# Arduino_nano_v3.net
KiCad netlist of a schematic drawn in Altium Designer
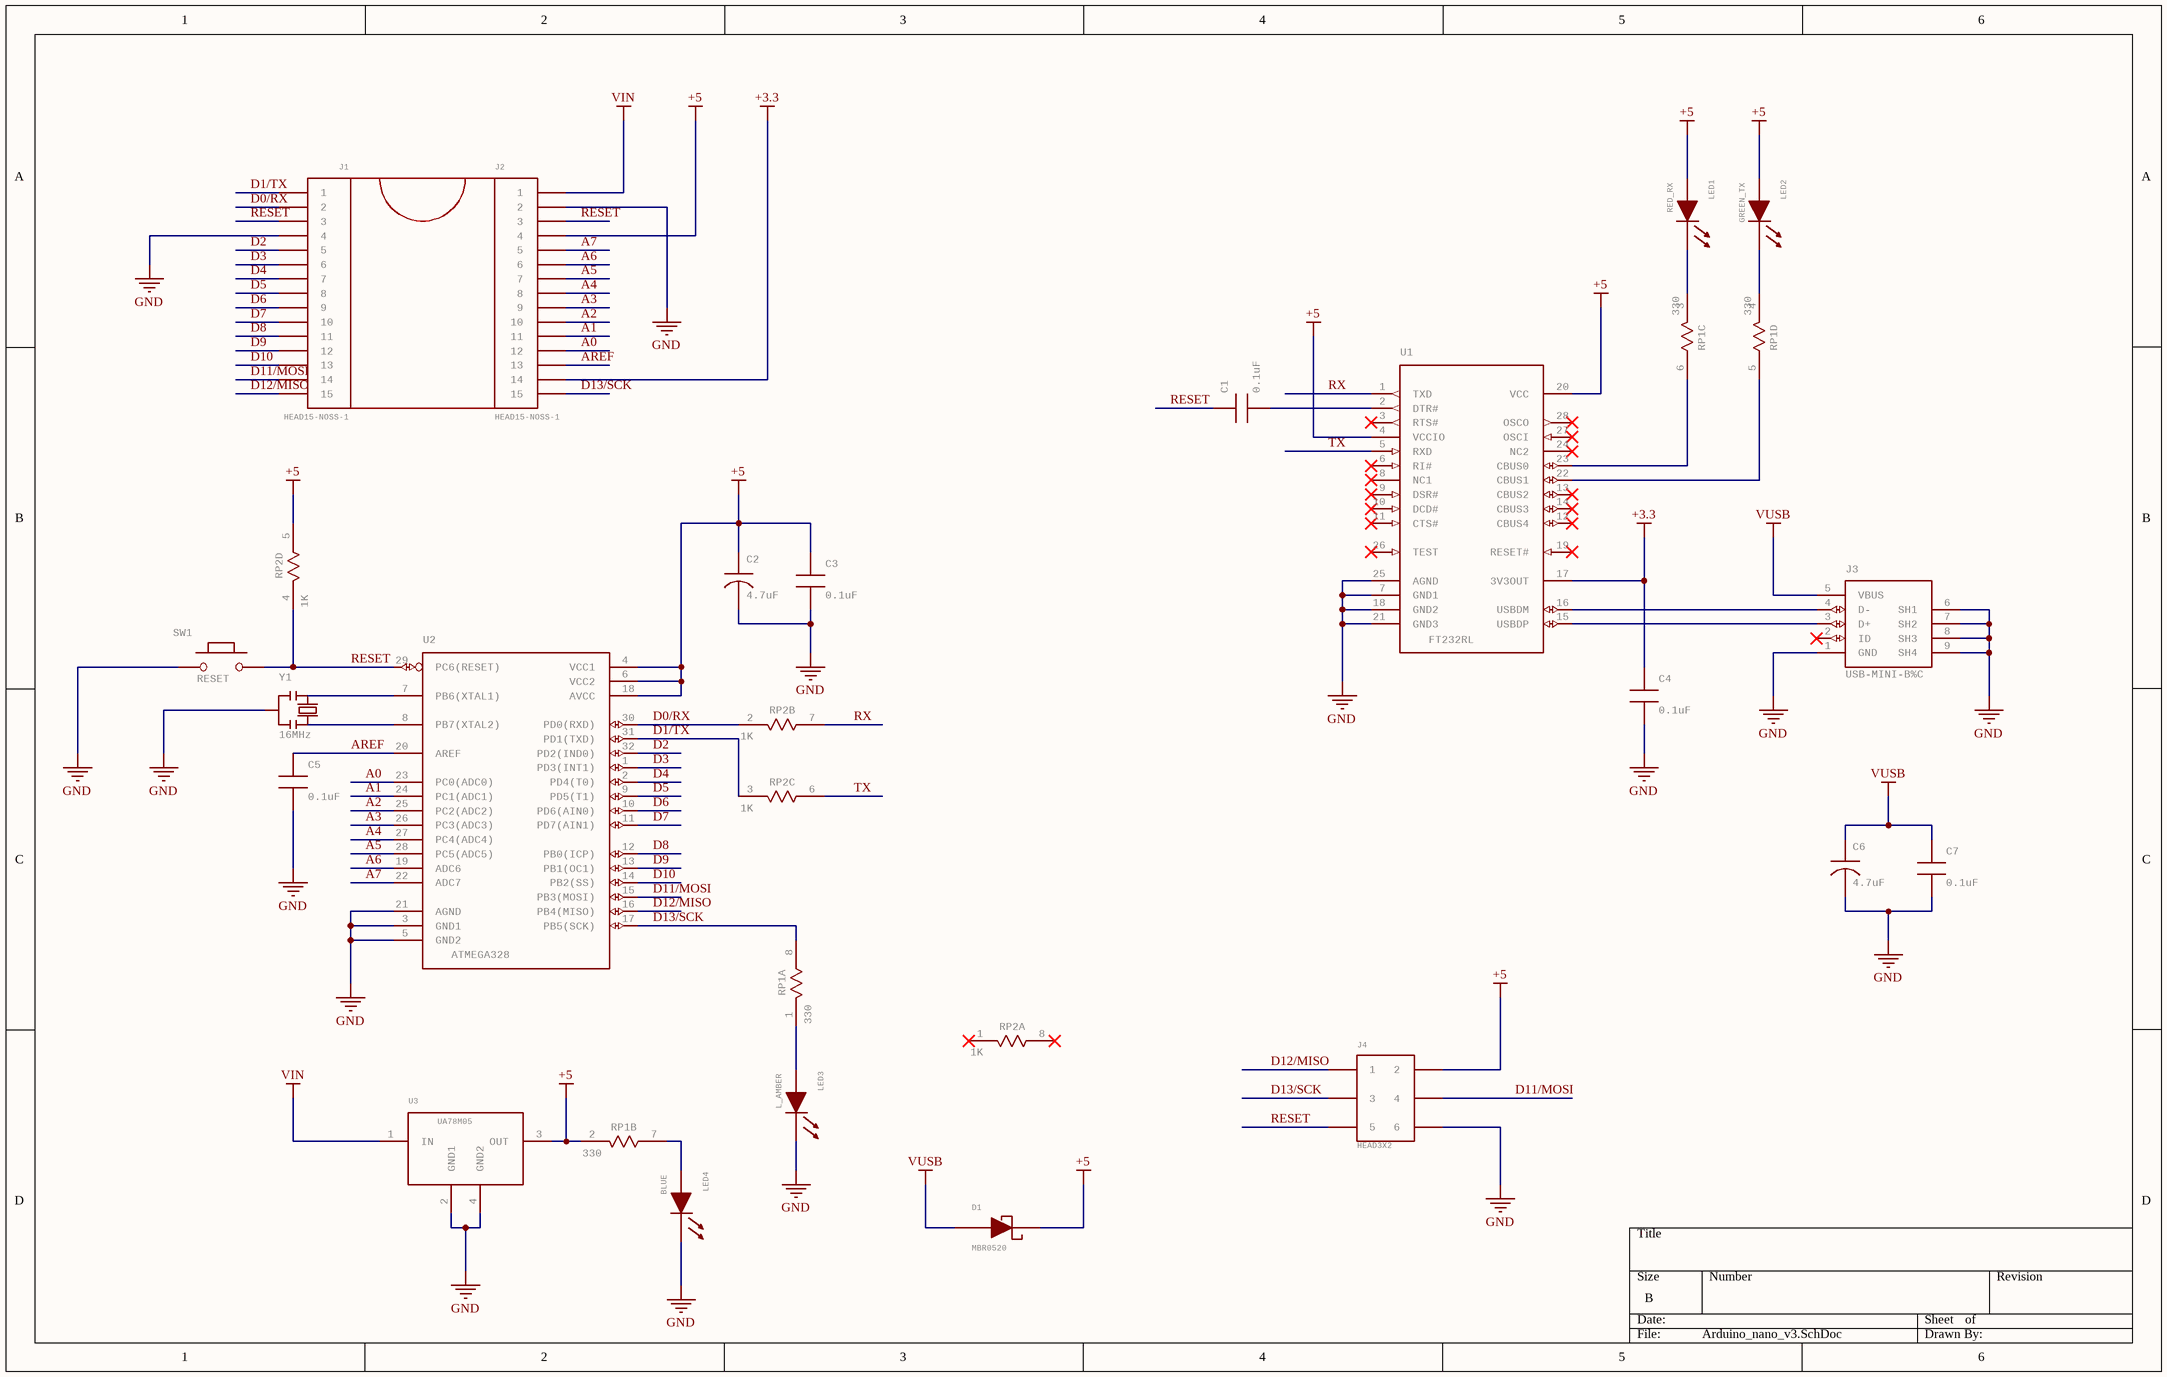
[diagram p0: Arduino_nano_v3.SchDoc]

(export (version "E")
  (design (tool "Eeschema 10.0.6"))
  (components
    (comp (ref "C1")
      (value "0.1uF")
      (footprint "CAP0805-NP")
      (description "Capacitor 0.1uF, 10%,50V")
      (fields (field (name "MANUFACTURER") "KEMET") (field (name "PART NUMBER") "C0805C104K5RACTU"))
      (libsource (lib "Arduino_Nano_2_V03_Schlib_Training") (part "CAP0805-NP"))
    )
    (comp (ref "C2")
      (value "4.7uF")
      (footprint "TAN-A")
      (description "Capacitor 4.7uF,10%,20V,TANT-A")
      (fields (field (name "MANUFACTURER") "AVX") (field (name "PART NUMBER") "TPSA475K020R1800"))
      (libsource (lib "Arduino_Nano_2_V03_Schlib_Training") (part "CAP-TANA-P"))
    )
    (comp (ref "C3")
      (value "0.1uF")
      (footprint "CAP0805-NP")
      (description "Capacitor 0.1uF, 10%,50V")
      (fields (field (name "MANUFACTURER") "KEMET") (field (name "PART NUMBER") "C0805C104K5RACTU"))
      (libsource (lib "Arduino_Nano_2_V03_Schlib_Training") (part "CAP0805-NP"))
    )
    (comp (ref "C4")
      (value "0.1uF")
      (footprint "CAP0805-NP")
      (description "Capacitor 0.1uF, 10%,50V")
      (fields (field (name "MANUFACTURER") "KEMET") (field (name "PART NUMBER") "C0805C104K5RACTU"))
      (libsource (lib "Arduino_Nano_2_V03_Schlib_Training") (part "CAP0805-NP"))
    )
    (comp (ref "C5")
      (value "0.1uF")
      (footprint "CAP0805-NP")
      (description "Capacitor 0.1uF, 10%,50V")
      (fields (field (name "MANUFACTURER") "KEMET") (field (name "PART NUMBER") "C0805C104K5RACTU"))
      (libsource (lib "Arduino_Nano_2_V03_Schlib_Training") (part "CAP0805-NP"))
    )
    (comp (ref "C6")
      (value "4.7uF")
      (footprint "TAN-A")
      (description "Capacitor 4.7uF,10%,20V,TANT-A")
      (fields (field (name "MANUFACTURER") "AVX") (field (name "PART NUMBER") "TPSA475K020R1800"))
      (libsource (lib "Arduino_Nano_2_V03_Schlib_Training") (part "CAP-TANA-P"))
    )
    (comp (ref "C7")
      (value "0.1uF")
      (footprint "CAP0805-NP")
      (description "Capacitor 0.1uF, 10%,50V")
      (fields (field (name "MANUFACTURER") "KEMET") (field (name "PART NUMBER") "C0805C104K5RACTU"))
      (libsource (lib "Arduino_Nano_2_V03_Schlib_Training") (part "CAP0805-NP"))
    )
    (comp (ref "D1")
      (value "MBR0520")
      (footprint "SOD-123")
      (description "MBR0520 SOD-123")
      (fields (field (name "MANUFACTURER") "ON Semiconductor") (field (name "PART NUMBER") "MBR0520LT1G"))
      (libsource (lib "Arduino_Nano_2_V03_Schlib_Training") (part "MBR0520"))
    )
    (comp (ref "J1")
      (value "HEAD15-NOSS-1")
      (footprint "HEAD15-NOSS-1")
      (description "HEAD15-NOSS 2.54mm")
      (fields (field (name "MANUFACTURER") "MOLEX") (field (name "PART NUMBER") "22-03-2151"))
      (libsource (lib "Arduino_Nano_2_V03_Schlib_Training") (part "HEAD15-NOSS-1"))
    )
    (comp (ref "J2")
      (value "HEAD15-NOSS-1")
      (footprint "HEAD15-NOSS-1")
      (description "HEAD15-NOSS 2.54mm")
      (fields (field (name "MANUFACTURER") "MOLEX") (field (name "PART NUMBER") "22-03-2151"))
      (libsource (lib "Arduino_Nano_2_V03_Schlib_Training") (part "HEAD15-NOSS-1"))
    )
    (comp (ref "J3")
      (value "USB-MINI-B%C")
      (footprint "USB-MINI-B_2")
      (description "USB-MINI-B")
      (fields (field (name "MANUFACTURER") "TE") (field (name "PART NUMBER") "1734035-2"))
      (libsource (lib "Arduino_Nano_2_V03_Schlib_Training") (part "USB-MINI-B"))
    )
    (comp (ref "J4")
      (value "HEAD3X2")
      (footprint "HEAD3X2")
      (description "HEAD3X2 2.54mm")
      (fields (field (name "MANUFACTURER") "3M") (field (name "PART NUMBER") "961206-6404-AR"))
      (libsource (lib "Arduino_Nano_2_V03_Schlib_Training") (part "HEAD3X2"))
    )
    (comp (ref "LED1")
      (value "RED_RX")
      (footprint "LED0805")
      (description "RED_RX LED0805")
      (fields (field (name "MANUFACTURER") "OS RAM") (field (name "PART NUMBER") "LH R974"))
      (libsource (lib "Arduino_Nano_2_V03_Schlib_Training") (part "LED0805_RED_LH-R974_OSRAM"))
    )
    (comp (ref "LED2")
      (value "GREEN_TX")
      (footprint "LED0805")
      (description "GREEN_TX LED0805")
      (fields (field (name "MANUFACTURER") "LITE-ON") (field (name "PART NUMBER") "LTST-C171GKT"))
      (libsource (lib "Arduino_Nano_2_V03_Schlib_Training") (part "LED0805_LTST-C171GKT_LITE-ON"))
    )
    (comp (ref "LED3")
      (value "L_AMBER")
      (footprint "LED0805")
      (description "L_AMBER LED0805")
      (fields (field (name "MANUFACTURER") "LITE-ON") (field (name "PART NUMBER") "LTST-C171AKT"))
      (libsource (lib "Arduino_Nano_2_V03_Schlib_Training") (part "LED0805_LTST-C171AKT_LITE-ON"))
    )
    (comp (ref "LED4")
      (value "BLUE")
      (footprint "LED0805")
      (description "BLUE LED0805")
      (fields (field (name "MANUFACTURER") "LITE-ON") (field (name "PART NUMBER") "LTST-C170TBKT"))
      (libsource (lib "Arduino_Nano_2_V03_Schlib_Training") (part "LED0805_LTST-C170TBKT_LITE-ON"))
    )
    (comp (ref "RP1")
      (value "330")
      (footprint "RES4NT")
      (description "330 RES4NT")
      (fields (field (name "MANUFACTURER") "Panasonic") (field (name "PART NUMBER") "EXB38V331JV"))
      (libsource (lib "Arduino_Nano_2_V03_Schlib_Training") (part "RES4NT_1"))
    )
    (comp (ref "RP2")
      (value "1K")
      (footprint "RES4NT")
      (description "1K RES4NT")
      (fields (field (name "MANUFACTURER") "Panasonic") (field (name "PART NUMBER") "EXB38V102JV"))
      (libsource (lib "Arduino_Nano_2_V03_Schlib_Training") (part "RES4NT"))
    )
    (comp (ref "SW1")
      (value "RESET")
      (footprint "157SW")
      (description "RESET PB157 157SW")
      (fields (field (name "MANUFACTURER") "OMRON") (field (name "PART NUMBER") "B3U-1000P"))
      (libsource (lib "Arduino_Nano_2_V03_Schlib_Training") (part "PB157"))
    )
    (comp (ref "U1")
      (value "FT232RL")
      (footprint "SSOP28")
      (description "FT232RL FT232RL SSOP28")
      (fields (field (name "MANUFACTURER") "FTDI"))
      (libsource (lib "Arduino_Nano_2_V03_Schlib_Training") (part "FT232RL"))
    )
    (comp (ref "U2")
      (value "ATMEGA328")
      (footprint "QFP032")
      (description "ATMEGA328P-AU ATMEGA168-20AU QFP032")
      (fields (field (name "MANUFACTURER") "Microchip") (field (name "PART NUMBER") "ATMEGA328P-AU"))
      (libsource (lib "Arduino_Nano_2_V03_Schlib_Training") (part "ATMEGA168-20AU"))
    )
    (comp (ref "U3")
      (value "UA78M05")
      (footprint "SOT223")
      (description "UA78M05 SOT223")
      (fields (field (name "MANUFACTURER") "TI") (field (name "PART NUMBER") "UA78M05CDCY"))
      (libsource (lib "Arduino_Nano_2_V03_Schlib_Training") (part "UA78M05"))
    )
    (comp (ref "Y1")
      (value "16MHz")
      (footprint "RESONATOR")
      (description "16MHz RESONATOR")
      (fields (field (name "MANUFACTURER") "Murata") (field (name "PART NUMBER") "CSTCE16M0V53A-R0"))
      (libsource (lib "Arduino_Nano_2_V03_Schlib_Training") (part "RESONATORMU"))
    )
  )
  (nets
    (net (code "1") (name "+3.3") (class "Default")
      (node (ref "C4") (pin "1") (pinfunction "1_1") (pintype "passive"))
      (node (ref "J2") (pin "14") (pinfunction "14_14") (pintype "passive"))
      (node (ref "U1") (pin "17") (pinfunction "3V3OUT_17") (pintype "power_in"))
    )
    (net (code "2") (name "+5") (class "Default")
      (node (ref "C2") (pin "1") (pinfunction "1_1") (pintype "passive"))
      (node (ref "C3") (pin "1") (pinfunction "1_1") (pintype "passive"))
      (node (ref "D1") (pin "1") (pinfunction "CA_1") (pintype "passive"))
      (node (ref "J2") (pin "4") (pinfunction "4_4") (pintype "passive"))
      (node (ref "J4") (pin "2") (pinfunction "2_2") (pintype "passive"))
      (node (ref "LED1") (pin "2") (pinfunction "AN_2") (pintype "passive"))
      (node (ref "LED2") (pin "2") (pinfunction "AN_2") (pintype "passive"))
      (node (ref "RP1") (pin "2") (pinfunction "1_2") (pintype "passive"))
      (node (ref "RP2") (pin "5") (pinfunction "2_5") (pintype "passive"))
      (node (ref "U1") (pin "20") (pinfunction "VCC_20") (pintype "power_in"))
      (node (ref "U1") (pin "4") (pinfunction "VCCIO_4") (pintype "power_in"))
      (node (ref "U2") (pin "18") (pinfunction "AVCC_18") (pintype "passive"))
      (node (ref "U2") (pin "4") (pinfunction "VCC1_4") (pintype "power_in"))
      (node (ref "U2") (pin "6") (pinfunction "VCC2_6") (pintype "power_in"))
      (node (ref "U3") (pin "3") (pinfunction "OUT_3") (pintype "power_in"))
    )
    (net (code "3") (name "/A0") (class "Default")
      (node (ref "J2") (pin "12") (pinfunction "12_12") (pintype "passive"))
      (node (ref "U2") (pin "23") (pinfunction "PC0(ADC0)_23") (pintype "passive"))
    )
    (net (code "4") (name "/A1") (class "Default")
      (node (ref "J2") (pin "11") (pinfunction "11_11") (pintype "passive"))
      (node (ref "U2") (pin "24") (pinfunction "PC1(ADC1)_24") (pintype "passive"))
    )
    (net (code "5") (name "/A2") (class "Default")
      (node (ref "J2") (pin "10") (pinfunction "10_10") (pintype "passive"))
      (node (ref "U2") (pin "25") (pinfunction "PC2(ADC2)_25") (pintype "passive"))
    )
    (net (code "6") (name "/A3") (class "Default")
      (node (ref "J2") (pin "9") (pinfunction "9_9") (pintype "passive"))
      (node (ref "U2") (pin "26") (pinfunction "PC3(ADC3)_26") (pintype "passive"))
    )
    (net (code "7") (name "/A4") (class "Default")
      (node (ref "J2") (pin "8") (pinfunction "8_8") (pintype "passive"))
      (node (ref "U2") (pin "27") (pinfunction "PC4(ADC4)_27") (pintype "passive"))
    )
    (net (code "8") (name "/A5") (class "Default")
      (node (ref "J2") (pin "7") (pinfunction "7_7") (pintype "passive"))
      (node (ref "U2") (pin "28") (pinfunction "PC5(ADC5)_28") (pintype "passive"))
    )
    (net (code "9") (name "/A6") (class "Default")
      (node (ref "J2") (pin "6") (pinfunction "6_6") (pintype "passive"))
      (node (ref "U2") (pin "19") (pinfunction "ADC6_19") (pintype "passive"))
    )
    (net (code "10") (name "/A7") (class "Default")
      (node (ref "J2") (pin "5") (pinfunction "5_5") (pintype "passive"))
      (node (ref "U2") (pin "22") (pinfunction "ADC7_22") (pintype "passive"))
    )
    (net (code "11") (name "/AREF") (class "Default")
      (node (ref "C5") (pin "1") (pinfunction "1_1") (pintype "passive"))
      (node (ref "J2") (pin "13") (pinfunction "13_13") (pintype "passive"))
      (node (ref "U2") (pin "20") (pinfunction "AREF_20") (pintype "passive"))
    )
    (net (code "12") (name "/D0{slash}RX") (class "Default")
      (node (ref "J1") (pin "2") (pinfunction "2_2") (pintype "passive"))
      (node (ref "RP2") (pin "2") (pinfunction "1_2") (pintype "passive"))
      (node (ref "U2") (pin "30") (pinfunction "PD0(RXD)_30") (pintype "bidirectional"))
    )
    (net (code "13") (name "/D1{slash}TX") (class "Default")
      (node (ref "J1") (pin "1") (pinfunction "1_1") (pintype "passive"))
      (node (ref "RP2") (pin "3") (pinfunction "1_3") (pintype "passive"))
      (node (ref "U2") (pin "31") (pinfunction "PD1(TXD)_31") (pintype "bidirectional"))
    )
    (net (code "14") (name "/D2") (class "Default")
      (node (ref "J1") (pin "5") (pinfunction "5_5") (pintype "passive"))
      (node (ref "U2") (pin "32") (pinfunction "PD2(IND0)_32") (pintype "bidirectional"))
    )
    (net (code "15") (name "/D3") (class "Default")
      (node (ref "J1") (pin "6") (pinfunction "6_6") (pintype "passive"))
      (node (ref "U2") (pin "1") (pinfunction "PD3(INT1)_1") (pintype "bidirectional"))
    )
    (net (code "16") (name "/D4") (class "Default")
      (node (ref "J1") (pin "7") (pinfunction "7_7") (pintype "passive"))
      (node (ref "U2") (pin "2") (pinfunction "PD4(T0)_2") (pintype "bidirectional"))
    )
    (net (code "17") (name "/D5") (class "Default")
      (node (ref "J1") (pin "8") (pinfunction "8_8") (pintype "passive"))
      (node (ref "U2") (pin "9") (pinfunction "PD5(T1)_9") (pintype "bidirectional"))
    )
    (net (code "18") (name "/D6") (class "Default")
      (node (ref "J1") (pin "9") (pinfunction "9_9") (pintype "passive"))
      (node (ref "U2") (pin "10") (pinfunction "PD6(AIN0)_10") (pintype "bidirectional"))
    )
    (net (code "19") (name "/D7") (class "Default")
      (node (ref "J1") (pin "10") (pinfunction "10_10") (pintype "passive"))
      (node (ref "U2") (pin "11") (pinfunction "PD7(AIN1)_11") (pintype "bidirectional"))
    )
    (net (code "20") (name "/D8") (class "Default")
      (node (ref "J1") (pin "11") (pinfunction "11_11") (pintype "passive"))
      (node (ref "U2") (pin "12") (pinfunction "PB0(ICP)_12") (pintype "bidirectional"))
    )
    (net (code "21") (name "/D9") (class "Default")
      (node (ref "J1") (pin "12") (pinfunction "12_12") (pintype "passive"))
      (node (ref "U2") (pin "13") (pinfunction "PB1(OC1)_13") (pintype "bidirectional"))
    )
    (net (code "22") (name "/D10") (class "Default")
      (node (ref "J1") (pin "13") (pinfunction "13_13") (pintype "passive"))
      (node (ref "U2") (pin "14") (pinfunction "PB2(SS)_14") (pintype "bidirectional"))
    )
    (net (code "23") (name "/D11{slash}MOSI") (class "Default")
      (node (ref "J1") (pin "14") (pinfunction "14_14") (pintype "passive"))
      (node (ref "J4") (pin "4") (pinfunction "4_4") (pintype "passive"))
      (node (ref "U2") (pin "15") (pinfunction "PB3(MOSI)_15") (pintype "bidirectional"))
    )
    (net (code "24") (name "/D12{slash}MISO") (class "Default")
      (node (ref "J1") (pin "15") (pinfunction "15_15") (pintype "passive"))
      (node (ref "J4") (pin "1") (pinfunction "1_1") (pintype "passive"))
      (node (ref "U2") (pin "16") (pinfunction "PB4(MISO)_16") (pintype "bidirectional"))
    )
    (net (code "25") (name "/D13{slash}SCK") (class "Default")
      (node (ref "J2") (pin "15") (pinfunction "15_15") (pintype "passive"))
      (node (ref "J4") (pin "3") (pinfunction "3_3") (pintype "passive"))
      (node (ref "RP1") (pin "8") (pinfunction "2_8") (pintype "passive"))
      (node (ref "U2") (pin "17") (pinfunction "PB5(SCK)_17") (pintype "bidirectional"))
    )
    (net (code "26") (name "/RESET") (class "Default")
      (node (ref "C1") (pin "1") (pinfunction "1_1") (pintype "passive"))
      (node (ref "J1") (pin "3") (pinfunction "3_3") (pintype "passive"))
      (node (ref "J2") (pin "3") (pinfunction "3_3") (pintype "passive"))
      (node (ref "J4") (pin "5") (pinfunction "5_5") (pintype "passive"))
      (node (ref "RP2") (pin "4") (pinfunction "1_4") (pintype "passive"))
      (node (ref "SW1") (pin "2") (pinfunction "2_2") (pintype "passive"))
      (node (ref "U2") (pin "29") (pinfunction "PC6(RESET)_29") (pintype "bidirectional"))
    )
    (net (code "27") (name "/RX") (class "Default")
      (node (ref "RP2") (pin "7") (pinfunction "2_7") (pintype "passive"))
      (node (ref "U1") (pin "1") (pinfunction "TXD_1") (pintype "output"))
    )
    (net (code "28") (name "/TX") (class "Default")
      (node (ref "RP2") (pin "6") (pinfunction "2_6") (pintype "passive"))
      (node (ref "U1") (pin "5") (pinfunction "RXD_5") (pintype "input"))
    )
    (net (code "29") (name "GND") (class "Default")
      (node (ref "C2") (pin "2") (pinfunction "2_2") (pintype "passive"))
      (node (ref "C3") (pin "2") (pinfunction "2_2") (pintype "passive"))
      (node (ref "C4") (pin "2") (pinfunction "2_2") (pintype "passive"))
      (node (ref "C5") (pin "2") (pinfunction "2_2") (pintype "passive"))
      (node (ref "C6") (pin "2") (pinfunction "2_2") (pintype "passive"))
      (node (ref "C7") (pin "2") (pinfunction "2_2") (pintype "passive"))
      (node (ref "J1") (pin "4") (pinfunction "4_4") (pintype "passive"))
      (node (ref "J2") (pin "2") (pinfunction "2_2") (pintype "passive"))
      (node (ref "J3") (pin "1") (pinfunction "GND_1") (pintype "passive"))
      (node (ref "J3") (pin "6") (pinfunction "SH1_6") (pintype "passive"))
      (node (ref "J3") (pin "7") (pinfunction "SH2_7") (pintype "passive"))
      (node (ref "J3") (pin "8") (pinfunction "SH3_8") (pintype "passive"))
      (node (ref "J3") (pin "9") (pinfunction "SH4_9") (pintype "passive"))
      (node (ref "J4") (pin "6") (pinfunction "6_6") (pintype "passive"))
      (node (ref "LED3") (pin "1") (pinfunction "CA_1") (pintype "passive"))
      (node (ref "LED4") (pin "1") (pinfunction "CA_1") (pintype "passive"))
      (node (ref "SW1") (pin "1") (pinfunction "1_1") (pintype "passive"))
      (node (ref "U1") (pin "18") (pinfunction "GND2_18") (pintype "power_in"))
      (node (ref "U1") (pin "21") (pinfunction "GND3_21") (pintype "power_in"))
      (node (ref "U1") (pin "25") (pinfunction "AGND_25") (pintype "power_in"))
      (node (ref "U1") (pin "7") (pinfunction "GND1_7") (pintype "power_in"))
      (node (ref "U2") (pin "21") (pinfunction "AGND_21") (pintype "passive"))
      (node (ref "U2") (pin "3") (pinfunction "GND1_3") (pintype "power_in"))
      (node (ref "U2") (pin "5") (pinfunction "GND2_5") (pintype "power_in"))
      (node (ref "U3") (pin "2") (pinfunction "GND1_2") (pintype "power_in"))
      (node (ref "U3") (pin "4") (pinfunction "GND2_4") (pintype "power_in"))
      (node (ref "Y1") (pin "2") (pinfunction "2_2") (pintype "passive"))
    )
    (net (code "30") (name "Net-(J3-D+)") (class "Default")
      (node (ref "J3") (pin "3") (pinfunction "D+_3") (pintype "bidirectional"))
      (node (ref "U1") (pin "15") (pinfunction "USBDP_15") (pintype "bidirectional"))
    )
    (net (code "31") (name "Net-(J3-D-)") (class "Default")
      (node (ref "J3") (pin "4") (pinfunction "D-_4") (pintype "bidirectional"))
      (node (ref "U1") (pin "16") (pinfunction "USBDM_16") (pintype "bidirectional"))
    )
    (net (code "32") (name "Net-(LED1-CA)") (class "Default")
      (node (ref "LED1") (pin "1") (pinfunction "CA_1") (pintype "passive"))
      (node (ref "RP1") (pin "3") (pinfunction "1_3") (pintype "passive"))
    )
    (net (code "33") (name "Net-(LED2-CA)") (class "Default")
      (node (ref "LED2") (pin "1") (pinfunction "CA_1") (pintype "passive"))
      (node (ref "RP1") (pin "4") (pinfunction "1_4") (pintype "passive"))
    )
    (net (code "34") (name "Net-(LED3-AN)") (class "Default")
      (node (ref "LED3") (pin "2") (pinfunction "AN_2") (pintype "passive"))
      (node (ref "RP1") (pin "1") (pinfunction "1_1") (pintype "passive"))
    )
    (net (code "35") (name "Net-(LED4-AN)") (class "Default")
      (node (ref "LED4") (pin "2") (pinfunction "AN_2") (pintype "passive"))
      (node (ref "RP1") (pin "7") (pinfunction "2_7") (pintype "passive"))
    )
    (net (code "36") (name "Net-(RP1C-2)") (class "Default")
      (node (ref "RP1") (pin "6") (pinfunction "2_6") (pintype "passive"))
      (node (ref "U1") (pin "23") (pinfunction "CBUS0_23") (pintype "bidirectional"))
    )
    (net (code "37") (name "Net-(RP1D-2)") (class "Default")
      (node (ref "RP1") (pin "5") (pinfunction "2_5") (pintype "passive"))
      (node (ref "U1") (pin "22") (pinfunction "CBUS1_22") (pintype "bidirectional"))
    )
    (net (code "38") (name "Net-(U1-DTR#)") (class "Default")
      (node (ref "C1") (pin "2") (pinfunction "2_2") (pintype "passive"))
      (node (ref "U1") (pin "2") (pinfunction "DTR#_2") (pintype "output"))
    )
    (net (code "39") (name "Net-(U2-PB6(XTAL1))") (class "Default")
      (node (ref "U2") (pin "7") (pinfunction "PB6(XTAL1)_7") (pintype "passive"))
      (node (ref "Y1") (pin "1") (pinfunction "1_1") (pintype "passive"))
    )
    (net (code "40") (name "Net-(U2-PB7(XTAL2))") (class "Default")
      (node (ref "U2") (pin "8") (pinfunction "PB7(XTAL2)_8") (pintype "passive"))
      (node (ref "Y1") (pin "3") (pinfunction "3_3") (pintype "passive"))
    )
    (net (code "41") (name "VIN") (class "Default")
      (node (ref "J2") (pin "1") (pinfunction "1_1") (pintype "passive"))
      (node (ref "U3") (pin "1") (pinfunction "IN_1") (pintype "power_in"))
    )
    (net (code "42") (name "VUSB") (class "Default")
      (node (ref "C6") (pin "1") (pinfunction "1_1") (pintype "passive"))
      (node (ref "C7") (pin "1") (pinfunction "1_1") (pintype "passive"))
      (node (ref "D1") (pin "2") (pinfunction "AN_2") (pintype "passive"))
      (node (ref "J3") (pin "5") (pinfunction "VBUS_5") (pintype "power_in"))
    )
    (net (code "43") (name "unconnected-(J3-ID-Pad2)") (class "Default")
      (node (ref "J3") (pin "2") (pinfunction "ID_2") (pintype "bidirectional+no_connect"))
    )
    (net (code "44") (name "unconnected-(RP2-Pad1)") (class "Default")
      (node (ref "RP2") (pin "1") (pinfunction "1_1") (pintype "passive+no_connect"))
    )
    (net (code "45") (name "unconnected-(RP2A-2-Pad8)") (class "Default")
      (node (ref "RP2") (pin "8") (pinfunction "2_8") (pintype "passive+no_connect"))
    )
    (net (code "46") (name "unconnected-(U1-CBUS2-Pad13)") (class "Default")
      (node (ref "U1") (pin "13") (pinfunction "CBUS2_13") (pintype "bidirectional+no_connect"))
    )
    (net (code "47") (name "unconnected-(U1-CBUS3-Pad14)") (class "Default")
      (node (ref "U1") (pin "14") (pinfunction "CBUS3_14") (pintype "bidirectional+no_connect"))
    )
    (net (code "48") (name "unconnected-(U1-CBUS4-Pad12)") (class "Default")
      (node (ref "U1") (pin "12") (pinfunction "CBUS4_12") (pintype "bidirectional+no_connect"))
    )
    (net (code "49") (name "unconnected-(U1-CTS#-Pad11)") (class "Default")
      (node (ref "U1") (pin "11") (pinfunction "CTS#_11") (pintype "input+no_connect"))
    )
    (net (code "50") (name "unconnected-(U1-DCD#-Pad10)") (class "Default")
      (node (ref "U1") (pin "10") (pinfunction "DCD#_10") (pintype "input+no_connect"))
    )
    (net (code "51") (name "unconnected-(U1-DSR#-Pad9)") (class "Default")
      (node (ref "U1") (pin "9") (pinfunction "DSR#_9") (pintype "input+no_connect"))
    )
    (net (code "52") (name "unconnected-(U1-NC1-Pad8)") (class "Default")
      (node (ref "U1") (pin "8") (pinfunction "NC1_8") (pintype "passive+no_connect"))
    )
    (net (code "53") (name "unconnected-(U1-NC2-Pad24)") (class "Default")
      (node (ref "U1") (pin "24") (pinfunction "NC2_24") (pintype "passive+no_connect"))
    )
    (net (code "54") (name "unconnected-(U1-OSCI-Pad27)") (class "Default")
      (node (ref "U1") (pin "27") (pinfunction "OSCI_27") (pintype "input+no_connect"))
    )
    (net (code "55") (name "unconnected-(U1-OSCO-Pad28)") (class "Default")
      (node (ref "U1") (pin "28") (pinfunction "OSCO_28") (pintype "output+no_connect"))
    )
    (net (code "56") (name "unconnected-(U1-RESET#-Pad19)") (class "Default")
      (node (ref "U1") (pin "19") (pinfunction "RESET#_19") (pintype "input+no_connect"))
    )
    (net (code "57") (name "unconnected-(U1-RI#-Pad6)") (class "Default")
      (node (ref "U1") (pin "6") (pinfunction "RI#_6") (pintype "input+no_connect"))
    )
    (net (code "58") (name "unconnected-(U1-RTS#-Pad3)") (class "Default")
      (node (ref "U1") (pin "3") (pinfunction "RTS#_3") (pintype "output+no_connect"))
    )
    (net (code "59") (name "unconnected-(U1-TEST-Pad26)") (class "Default")
      (node (ref "U1") (pin "26") (pinfunction "TEST_26") (pintype "input+no_connect"))
    )
  )
)
